# g_plus_shield_v2.net
KiCad netlist of a schematic drawn in EAGLE
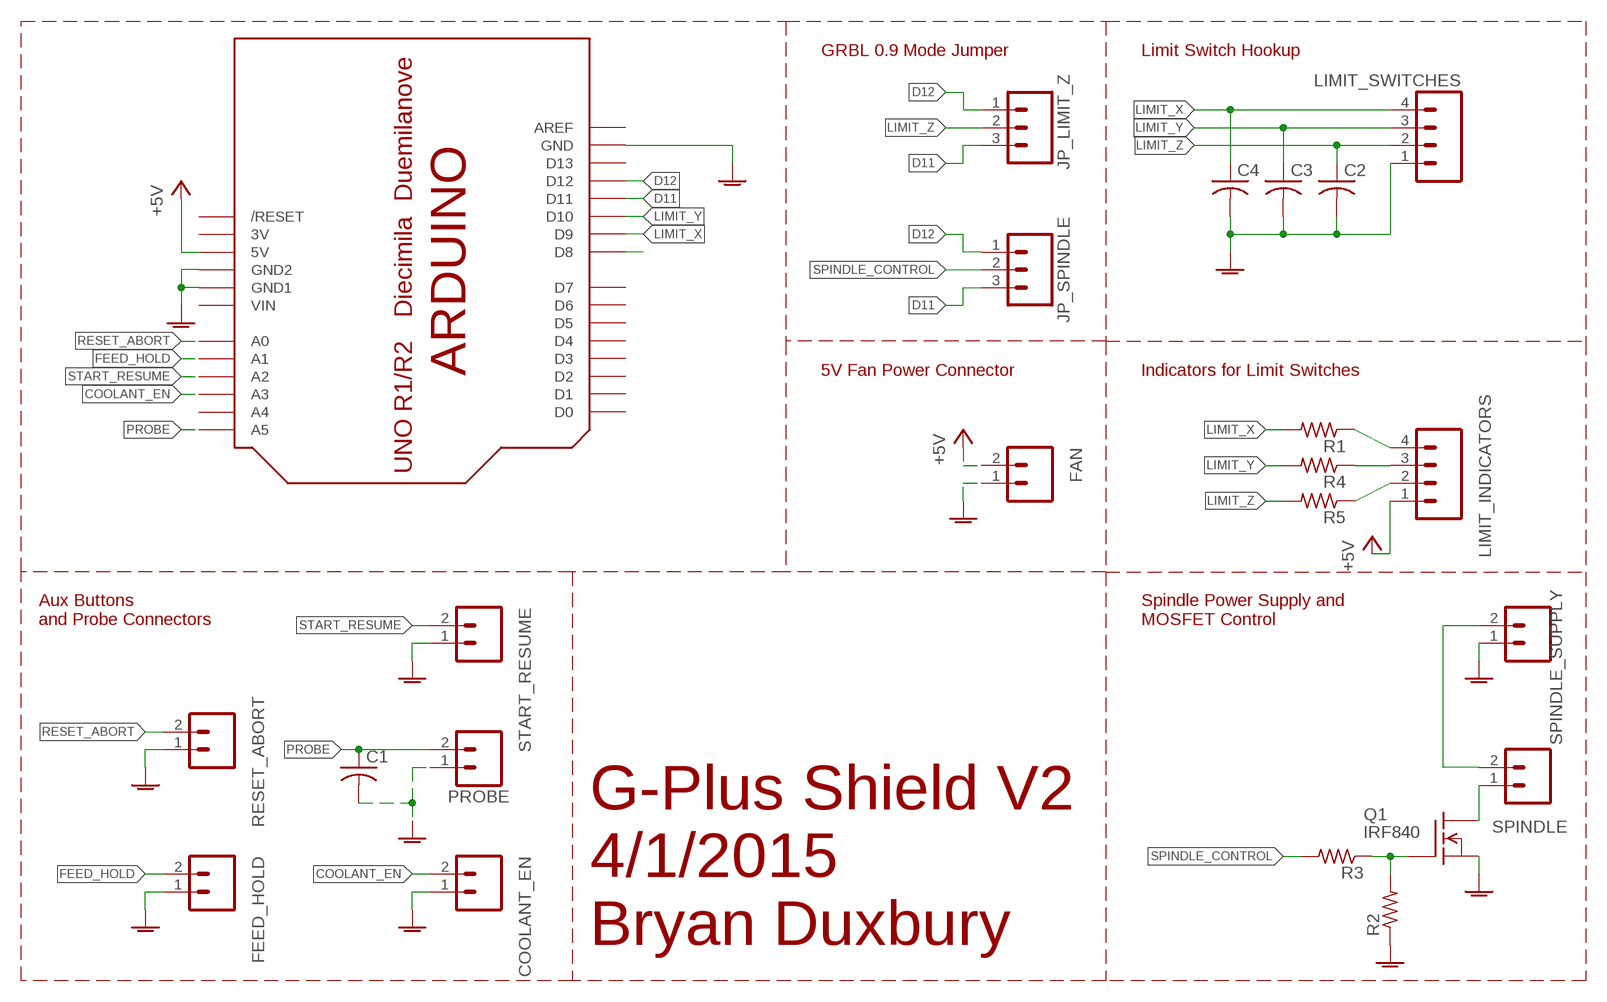
[diagram p0: schematic, sheet 1]

(export (version "E")
  (design (tool "Eeschema 10.0.6"))
  (components
    (comp (ref "C1")
      (value "C-US050-024X044")
      (footprint "eagle-import:C050-024X044")
      (libsource (lib "eagle-import") (part "C-US050-024X044"))
    )
    (comp (ref "C2")
      (value "C-US050-024X044")
      (footprint "eagle-import:C050-024X044")
      (libsource (lib "eagle-import") (part "C-US050-024X044"))
    )
    (comp (ref "C3")
      (value "C-US050-024X044")
      (footprint "eagle-import:C050-024X044")
      (libsource (lib "eagle-import") (part "C-US050-024X044"))
    )
    (comp (ref "C4")
      (value "C-US050-024X044")
      (footprint "eagle-import:C050-024X044")
      (libsource (lib "eagle-import") (part "C-US050-024X044"))
    )
    (comp (ref "COOLANT_EN")
      (value "M02POLAR")
      (footprint "eagle-import:MOLEX-1X2")
      (libsource (lib "eagle-import") (part "M02POLAR"))
    )
    (comp (ref "FAN")
      (value "M02POLAR")
      (footprint "eagle-import:MOLEX-1X2")
      (libsource (lib "eagle-import") (part "M02POLAR"))
    )
    (comp (ref "FEED_HOLD")
      (value "M02POLAR")
      (footprint "eagle-import:MOLEX-1X2")
      (libsource (lib "eagle-import") (part "M02POLAR"))
    )
    (comp (ref "JP_LIMIT_Z")
      (value "M03POLAR")
      (footprint "eagle-import:MOLEX-1X3")
      (libsource (lib "eagle-import") (part "M03POLAR"))
    )
    (comp (ref "JP_SPINDLE")
      (value "M03POLAR")
      (footprint "eagle-import:MOLEX-1X3")
      (libsource (lib "eagle-import") (part "M03POLAR"))
    )
    (comp (ref "LIMIT_INDICATORS")
      (value "M04POLAR")
      (footprint "eagle-import:MOLEX-1X4")
      (libsource (lib "eagle-import") (part "M04POLAR"))
    )
    (comp (ref "LIMIT_SWITCHES")
      (value "M04POLAR")
      (footprint "eagle-import:MOLEX-1X4")
      (libsource (lib "eagle-import") (part "M04POLAR"))
    )
    (comp (ref "PROBE")
      (value "M02POLAR")
      (footprint "eagle-import:MOLEX-1X2")
      (libsource (lib "eagle-import") (part "M02POLAR"))
    )
    (comp (ref "Q1")
      (value "IRF840")
      (footprint "eagle-import:TO220")
      (libsource (lib "eagle-import") (part "IRF840"))
    )
    (comp (ref "R1")
      (value "R-US_0207/7")
      (footprint "eagle-import:0207_7")
      (libsource (lib "eagle-import") (part "R-US_0207/7"))
    )
    (comp (ref "R2")
      (value "R-US_0207/7")
      (footprint "eagle-import:0207_7")
      (libsource (lib "eagle-import") (part "R-US_0207/7"))
    )
    (comp (ref "R3")
      (value "R-US_0207/7")
      (footprint "eagle-import:0207_7")
      (libsource (lib "eagle-import") (part "R-US_0207/7"))
    )
    (comp (ref "R4")
      (value "R-US_0207/7")
      (footprint "eagle-import:0207_7")
      (libsource (lib "eagle-import") (part "R-US_0207/7"))
    )
    (comp (ref "R5")
      (value "R-US_0207/7")
      (footprint "eagle-import:0207_7")
      (libsource (lib "eagle-import") (part "R-US_0207/7"))
    )
    (comp (ref "RESET_ABORT")
      (value "M02POLAR")
      (footprint "eagle-import:MOLEX-1X2")
      (libsource (lib "eagle-import") (part "M02POLAR"))
    )
    (comp (ref "SPINDLE")
      (value "M02POLAR")
      (footprint "eagle-import:MOLEX-1X2")
      (libsource (lib "eagle-import") (part "M02POLAR"))
    )
    (comp (ref "SPINDLE_SUPPLY")
      (value "M02POLAR")
      (footprint "eagle-import:MOLEX-1X2")
      (libsource (lib "eagle-import") (part "M02POLAR"))
    )
    (comp (ref "START_RESUME")
      (value "M02POLAR")
      (footprint "eagle-import:MOLEX-1X2")
      (libsource (lib "eagle-import") (part "M02POLAR"))
    )
    (comp (ref "U$1")
      (value "ARDUINO-NODIM")
      (footprint "eagle-import:ARDUINO-NODIM")
      (libsource (lib "eagle-import") (part "ARDUINO-NODIM"))
    )
  )
  (nets
    (net (code "1") (name "+5V") (class "Default")
      (node (ref "FAN") (pin "2") (pinfunction "2_2") (pintype "passive"))
      (node (ref "LIMIT_INDICATORS") (pin "1") (pinfunction "1_1") (pintype "passive"))
      (node (ref "U$1") (pin "5V") (pinfunction "5V_5V") (pintype "power_in"))
    )
    (net (code "2") (name "/3V") (class "Default")
      (node (ref "U$1") (pin "3V") (pinfunction "3V_3V") (pintype "power_in"))
    )
    (net (code "3") (name "/VIN") (class "Default")
      (node (ref "U$1") (pin "VIN") (pinfunction "VIN_VIN") (pintype "power_in"))
    )
    (net (code "4") (name "COOLANT_EN") (class "Default")
      (node (ref "COOLANT_EN") (pin "2") (pinfunction "2_2") (pintype "passive"))
      (node (ref "U$1") (pin "A3") (pinfunction "A3_A3") (pintype "bidirectional"))
    )
    (net (code "5") (name "D11") (class "Default")
      (node (ref "JP_LIMIT_Z") (pin "3") (pinfunction "3_3") (pintype "passive"))
      (node (ref "JP_SPINDLE") (pin "3") (pinfunction "3_3") (pintype "passive"))
      (node (ref "U$1") (pin "D11") (pinfunction "D11_D11") (pintype "bidirectional"))
    )
    (net (code "6") (name "D12") (class "Default")
      (node (ref "JP_LIMIT_Z") (pin "1") (pinfunction "1_1") (pintype "passive"))
      (node (ref "JP_SPINDLE") (pin "1") (pinfunction "1_1") (pintype "passive"))
      (node (ref "U$1") (pin "D12") (pinfunction "D12_D12") (pintype "bidirectional"))
    )
    (net (code "7") (name "FEED_HOLD") (class "Default")
      (node (ref "FEED_HOLD") (pin "2") (pinfunction "2_2") (pintype "passive"))
      (node (ref "U$1") (pin "A1") (pinfunction "A1_A1") (pintype "bidirectional"))
    )
    (net (code "8") (name "GNDA") (class "Default")
      (node (ref "C1") (pin "2") (pinfunction "2_2") (pintype "passive"))
      (node (ref "C2") (pin "2") (pinfunction "2_2") (pintype "passive"))
      (node (ref "C3") (pin "2") (pinfunction "2_2") (pintype "passive"))
      (node (ref "C4") (pin "2") (pinfunction "2_2") (pintype "passive"))
      (node (ref "COOLANT_EN") (pin "1") (pinfunction "1_1") (pintype "passive"))
      (node (ref "FAN") (pin "1") (pinfunction "1_1") (pintype "passive"))
      (node (ref "FEED_HOLD") (pin "1") (pinfunction "1_1") (pintype "passive"))
      (node (ref "LIMIT_SWITCHES") (pin "1") (pinfunction "1_1") (pintype "passive"))
      (node (ref "PROBE") (pin "1") (pinfunction "1_1") (pintype "passive"))
      (node (ref "Q1") (pin "3") (pinfunction "S_3") (pintype "passive"))
      (node (ref "R2") (pin "1") (pinfunction "1_1") (pintype "passive"))
      (node (ref "RESET_ABORT") (pin "1") (pinfunction "1_1") (pintype "passive"))
      (node (ref "SPINDLE_SUPPLY") (pin "1") (pinfunction "1_1") (pintype "passive"))
      (node (ref "START_RESUME") (pin "1") (pinfunction "1_1") (pintype "passive"))
      (node (ref "U$1") (pin "GND") (pinfunction "GND_GND") (pintype "power_in"))
      (node (ref "U$1") (pin "GND1") (pinfunction "GND1_GND1") (pintype "power_in"))
      (node (ref "U$1") (pin "GND2") (pinfunction "GND2_GND2") (pintype "power_in"))
    )
    (net (code "9") (name "LIMIT_X") (class "Default")
      (node (ref "C4") (pin "1") (pinfunction "1_1") (pintype "passive"))
      (node (ref "LIMIT_SWITCHES") (pin "4") (pinfunction "4_4") (pintype "passive"))
      (node (ref "R1") (pin "2") (pinfunction "2_2") (pintype "passive"))
      (node (ref "U$1") (pin "D9") (pinfunction "D9_D9") (pintype "bidirectional"))
    )
    (net (code "10") (name "LIMIT_Y") (class "Default")
      (node (ref "C3") (pin "1") (pinfunction "1_1") (pintype "passive"))
      (node (ref "LIMIT_SWITCHES") (pin "3") (pinfunction "3_3") (pintype "passive"))
      (node (ref "R4") (pin "2") (pinfunction "2_2") (pintype "passive"))
      (node (ref "U$1") (pin "D10") (pinfunction "D10_D10") (pintype "bidirectional"))
    )
    (net (code "11") (name "LIMIT_Z") (class "Default")
      (node (ref "C2") (pin "1") (pinfunction "1_1") (pintype "passive"))
      (node (ref "JP_LIMIT_Z") (pin "2") (pinfunction "2_2") (pintype "passive"))
      (node (ref "LIMIT_SWITCHES") (pin "2") (pinfunction "2_2") (pintype "passive"))
      (node (ref "R5") (pin "2") (pinfunction "2_2") (pintype "passive"))
    )
    (net (code "12") (name "Net-(LIMIT_INDICATORS-Pad2)") (class "Default")
      (node (ref "LIMIT_INDICATORS") (pin "2") (pinfunction "2_2") (pintype "passive"))
      (node (ref "R5") (pin "1") (pinfunction "1_1") (pintype "passive"))
    )
    (net (code "13") (name "Net-(LIMIT_INDICATORS-Pad3)") (class "Default")
      (node (ref "LIMIT_INDICATORS") (pin "3") (pinfunction "3_3") (pintype "passive"))
      (node (ref "R4") (pin "1") (pinfunction "1_1") (pintype "passive"))
    )
    (net (code "14") (name "Net-(LIMIT_INDICATORS-Pad4)") (class "Default")
      (node (ref "LIMIT_INDICATORS") (pin "4") (pinfunction "4_4") (pintype "passive"))
      (node (ref "R1") (pin "1") (pinfunction "1_1") (pintype "passive"))
    )
    (net (code "15") (name "Net-(Q1-D)") (class "Default")
      (node (ref "Q1") (pin "2") (pinfunction "D_2") (pintype "passive"))
      (node (ref "SPINDLE") (pin "1") (pinfunction "1_1") (pintype "passive"))
    )
    (net (code "16") (name "Net-(Q1-G)") (class "Default")
      (node (ref "Q1") (pin "1") (pinfunction "G_1") (pintype "passive"))
      (node (ref "R2") (pin "2") (pinfunction "2_2") (pintype "passive"))
      (node (ref "R3") (pin "1") (pinfunction "1_1") (pintype "passive"))
    )
    (net (code "17") (name "Net-(SPINDLE-Pad2)") (class "Default")
      (node (ref "SPINDLE") (pin "2") (pinfunction "2_2") (pintype "passive"))
      (node (ref "SPINDLE_SUPPLY") (pin "2") (pinfunction "2_2") (pintype "passive"))
    )
    (net (code "18") (name "PROBE") (class "Default")
      (node (ref "C1") (pin "1") (pinfunction "1_1") (pintype "passive"))
      (node (ref "PROBE") (pin "2") (pinfunction "2_2") (pintype "passive"))
      (node (ref "U$1") (pin "A5") (pinfunction "A5_A5") (pintype "bidirectional"))
    )
    (net (code "19") (name "RESET_ABORT") (class "Default")
      (node (ref "RESET_ABORT") (pin "2") (pinfunction "2_2") (pintype "passive"))
      (node (ref "U$1") (pin "A0") (pinfunction "A0_A0") (pintype "bidirectional"))
    )
    (net (code "20") (name "SPINDLE_CONTROL") (class "Default")
      (node (ref "JP_SPINDLE") (pin "2") (pinfunction "2_2") (pintype "passive"))
      (node (ref "R3") (pin "2") (pinfunction "2_2") (pintype "passive"))
    )
    (net (code "21") (name "START_RESUME") (class "Default")
      (node (ref "START_RESUME") (pin "2") (pinfunction "2_2") (pintype "passive"))
      (node (ref "U$1") (pin "A2") (pinfunction "A2_A2") (pintype "bidirectional"))
    )
    (net (code "22") (name "unconnected-(U$1-PadA4)") (class "Default")
      (node (ref "U$1") (pin "A4") (pinfunction "A4_A4") (pintype "bidirectional"))
    )
    (net (code "23") (name "unconnected-(U$1-PadAREF)") (class "Default")
      (node (ref "U$1") (pin "AREF") (pinfunction "AREF_AREF") (pintype "bidirectional"))
    )
    (net (code "24") (name "unconnected-(U$1-PadD0)") (class "Default")
      (node (ref "U$1") (pin "D0") (pinfunction "D0_D0") (pintype "bidirectional"))
    )
    (net (code "25") (name "unconnected-(U$1-PadD1)") (class "Default")
      (node (ref "U$1") (pin "D1") (pinfunction "D1_D1") (pintype "bidirectional"))
    )
    (net (code "26") (name "unconnected-(U$1-PadD2)") (class "Default")
      (node (ref "U$1") (pin "D2") (pinfunction "D2_D2") (pintype "bidirectional"))
    )
    (net (code "27") (name "unconnected-(U$1-PadD3)") (class "Default")
      (node (ref "U$1") (pin "D3") (pinfunction "D3_D3") (pintype "bidirectional"))
    )
    (net (code "28") (name "unconnected-(U$1-PadD4)") (class "Default")
      (node (ref "U$1") (pin "D4") (pinfunction "D4_D4") (pintype "bidirectional"))
    )
    (net (code "29") (name "unconnected-(U$1-PadD5)") (class "Default")
      (node (ref "U$1") (pin "D5") (pinfunction "D5_D5") (pintype "bidirectional"))
    )
    (net (code "30") (name "unconnected-(U$1-PadD6)") (class "Default")
      (node (ref "U$1") (pin "D6") (pinfunction "D6_D6") (pintype "bidirectional"))
    )
    (net (code "31") (name "unconnected-(U$1-PadD7)") (class "Default")
      (node (ref "U$1") (pin "D7") (pinfunction "D7_D7") (pintype "bidirectional"))
    )
    (net (code "32") (name "unconnected-(U$1-PadD8)") (class "Default")
      (node (ref "U$1") (pin "D8") (pinfunction "D8_D8") (pintype "bidirectional"))
    )
    (net (code "33") (name "unconnected-(U$1-PadD13)") (class "Default")
      (node (ref "U$1") (pin "D13") (pinfunction "D13_D13") (pintype "bidirectional"))
    )
    (net (code "34") (name "unconnected-(U$1-{slash}RESET-PadRESET)") (class "Default")
      (node (ref "U$1") (pin "RESET") (pinfunction "/RESET_RESET") (pintype "bidirectional"))
    )
  )
)
